# Audio_player_1_0.net
KiCad netlist of a schematic drawn in EAGLE
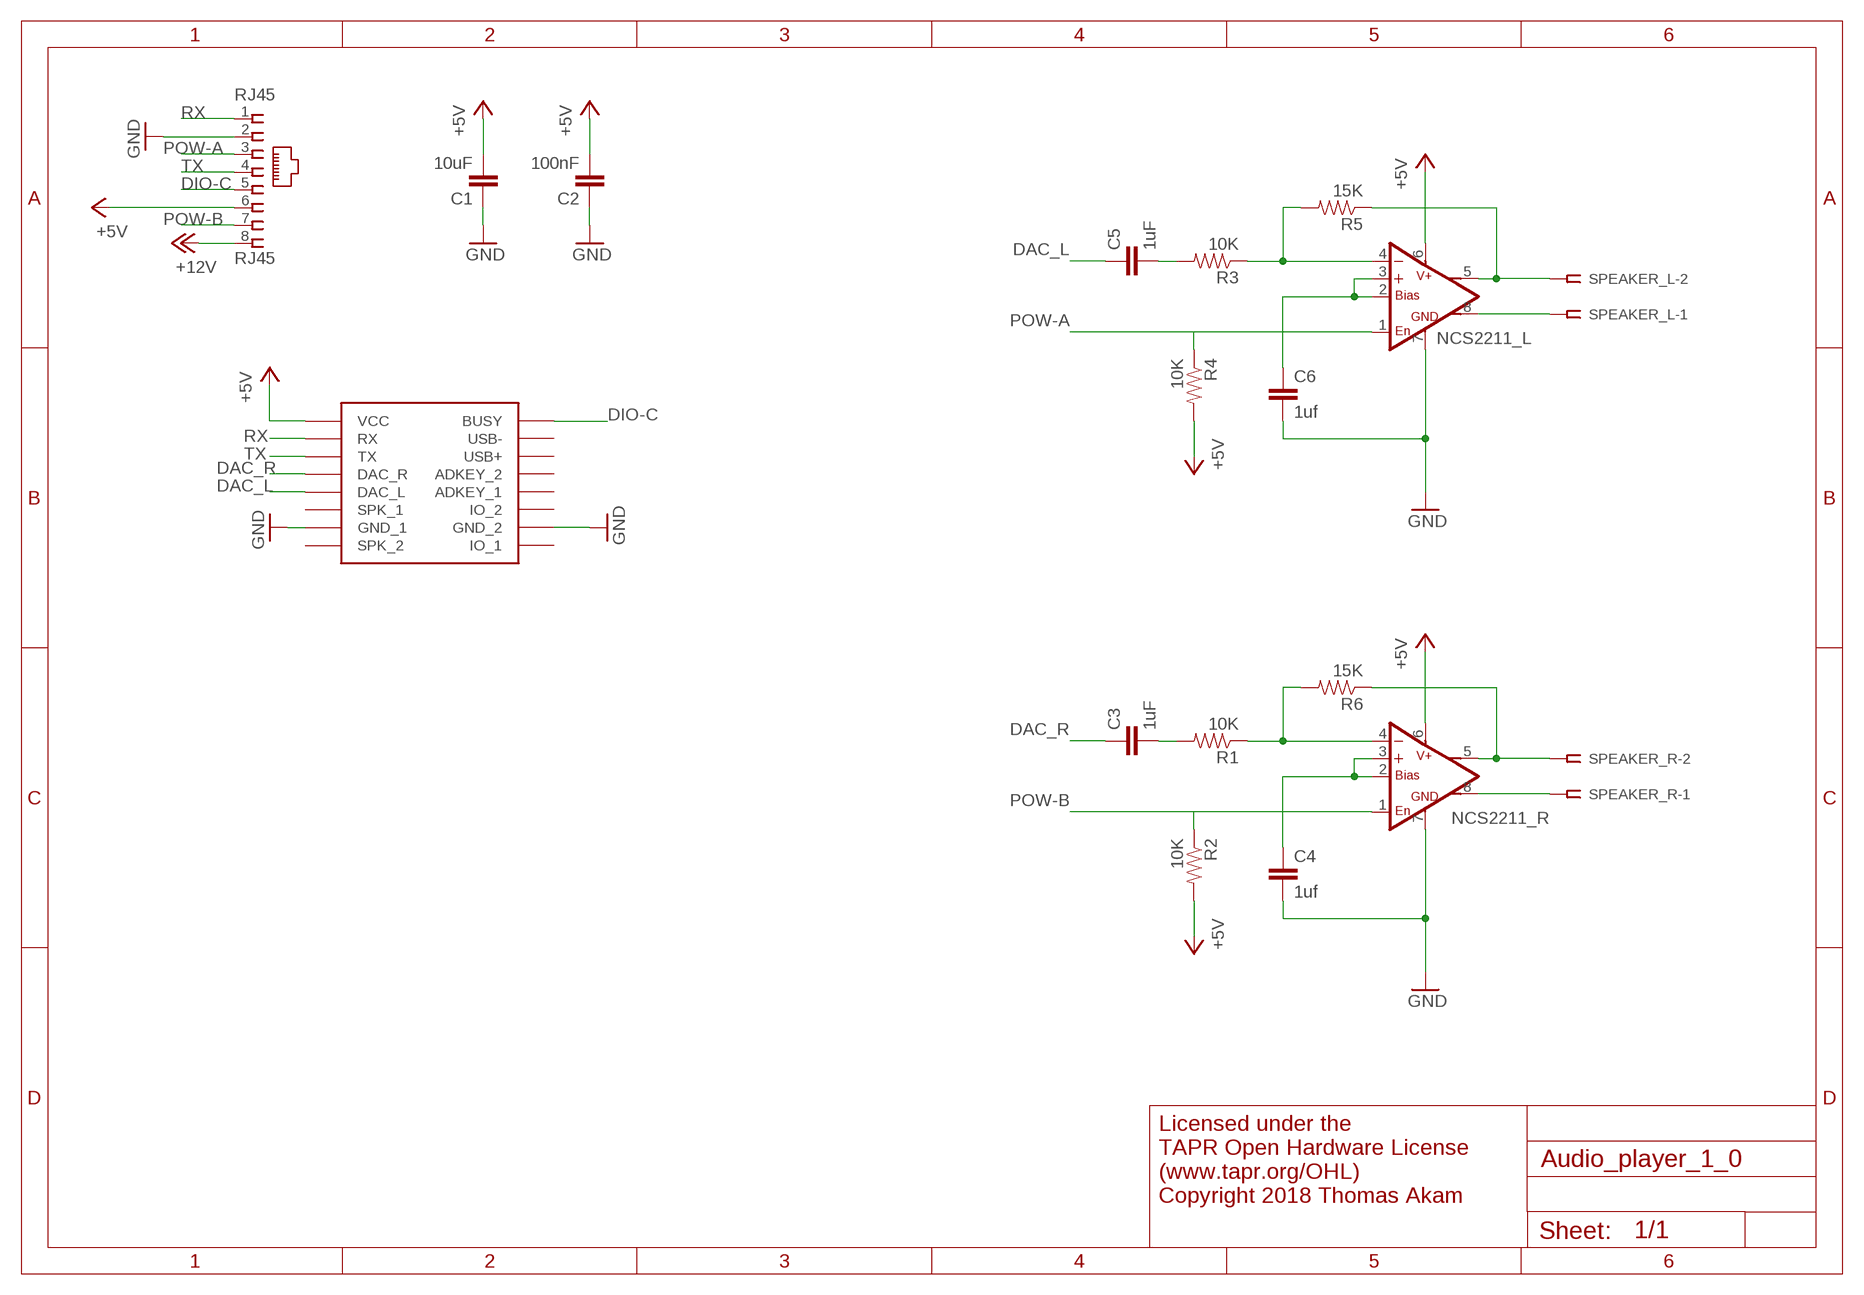
[diagram p0: schematic, sheet 1]

(export (version "E")
  (design (tool "Eeschema 10.0.6"))
  (components
    (comp (ref "C1")
      (value "10uF")
      (footprint "eagle-import:C0805")
      (libsource (lib "eagle-import") (part "C-EUC0805"))
    )
    (comp (ref "C2")
      (value "100nF")
      (footprint "eagle-import:C0805")
      (libsource (lib "eagle-import") (part "C-EUC0805"))
    )
    (comp (ref "C3")
      (value "1uF")
      (footprint "eagle-import:C0805")
      (libsource (lib "eagle-import") (part "C-EUC0805"))
    )
    (comp (ref "C4")
      (value "1uf")
      (footprint "eagle-import:C0805")
      (libsource (lib "eagle-import") (part "C-EUC0805"))
    )
    (comp (ref "C5")
      (value "1uF")
      (footprint "eagle-import:C0805")
      (libsource (lib "eagle-import") (part "C-EUC0805"))
    )
    (comp (ref "C6")
      (value "1uf")
      (footprint "eagle-import:C0805")
      (libsource (lib "eagle-import") (part "C-EUC0805"))
    )
    (comp (ref "NCS2211_L")
      (value "NCS22111M")
      (footprint "eagle-import:SO08")
      (libsource (lib "eagle-import") (part "NCS2211M1"))
    )
    (comp (ref "NCS2211_R")
      (value "NCS22111M")
      (footprint "eagle-import:SO08")
      (libsource (lib "eagle-import") (part "NCS2211M1"))
    )
    (comp (ref "R1")
      (value "10K")
      (footprint "eagle-import:0805")
      (libsource (lib "eagle-import") (part "0.3OHM-1/8W-1%(0805)"))
    )
    (comp (ref "R2")
      (value "10K")
      (footprint "eagle-import:0805")
      (libsource (lib "eagle-import") (part "0.3OHM-1/8W-1%(0805)"))
    )
    (comp (ref "R3")
      (value "10K")
      (footprint "eagle-import:0805")
      (libsource (lib "eagle-import") (part "0.3OHM-1/8W-1%(0805)"))
    )
    (comp (ref "R4")
      (value "10K")
      (footprint "eagle-import:0805")
      (libsource (lib "eagle-import") (part "0.3OHM-1/8W-1%(0805)"))
    )
    (comp (ref "R5")
      (value "15K")
      (footprint "eagle-import:0805")
      (libsource (lib "eagle-import") (part "0.3OHM-1/8W-1%(0805)"))
    )
    (comp (ref "R6")
      (value "15K")
      (footprint "eagle-import:0805")
      (libsource (lib "eagle-import") (part "0.3OHM-1/8W-1%(0805)"))
    )
    (comp (ref "RJ45")
      (value "RJ45")
      (footprint "eagle-import:RJ45-NO-SHIELD-VERTICAL")
      (libsource (lib "eagle-import") (part "RJ45VERTICAL"))
    )
    (comp (ref "SPEAKER_L")
      (value "SSW-102-02-S-S-RA")
      (footprint "eagle-import:SSW-102-02-S-S-RA")
      (libsource (lib "eagle-import") (part "SSW-102-02-S-S-RA"))
    )
    (comp (ref "SPEAKER_R")
      (value "SSW-102-02-S-S-RA")
      (footprint "eagle-import:SSW-102-02-S-S-RA")
      (libsource (lib "eagle-import") (part "SSW-102-02-S-S-RA"))
    )
    (comp (ref "U$1")
      (value "DFPLAYER")
      (footprint "eagle-import:DFPLAYER")
      (libsource (lib "eagle-import") (part "DFPLAYER"))
    )
  )
  (nets
    (net (code "1") (name "+5V") (class "Default")
      (node (ref "C1") (pin "2") (pinfunction "2_2") (pintype "passive"))
      (node (ref "C2") (pin "2") (pinfunction "2_2") (pintype "passive"))
      (node (ref "NCS2211_L") (pin "6") (pinfunction "VS_6") (pintype "power_in"))
      (node (ref "NCS2211_R") (pin "6") (pinfunction "VS_6") (pintype "power_in"))
      (node (ref "R2") (pin "2") (pinfunction "2_2") (pintype "passive"))
      (node (ref "R4") (pin "2") (pinfunction "2_2") (pintype "passive"))
      (node (ref "RJ45") (pin "6") (pinfunction "6_6") (pintype "passive"))
      (node (ref "U$1") (pin "VCC") (pinfunction "VCC_VCC") (pintype "bidirectional"))
    )
    (net (code "2") (name "+12V") (class "Default")
      (node (ref "RJ45") (pin "8") (pinfunction "8_8") (pintype "passive"))
    )
    (net (code "3") (name "/DAC_L") (class "Default")
      (node (ref "C5") (pin "1") (pinfunction "1_1") (pintype "passive"))
      (node (ref "U$1") (pin "DAC_L") (pinfunction "DAC_L_DAC_L") (pintype "bidirectional"))
    )
    (net (code "4") (name "/DAC_R") (class "Default")
      (node (ref "C3") (pin "1") (pinfunction "1_1") (pintype "passive"))
      (node (ref "U$1") (pin "DAC_R") (pinfunction "DAC_R_DAC_R") (pintype "bidirectional"))
    )
    (net (code "5") (name "/DIO-C") (class "Default")
      (node (ref "RJ45") (pin "5") (pinfunction "5_5") (pintype "passive"))
      (node (ref "U$1") (pin "BUSY") (pinfunction "BUSY_BUSY") (pintype "bidirectional"))
    )
    (net (code "6") (name "/POW-A") (class "Default")
      (node (ref "NCS2211_L") (pin "1") (pinfunction "ENABLE_1") (pintype "passive"))
      (node (ref "R4") (pin "1") (pinfunction "1_1") (pintype "passive"))
      (node (ref "RJ45") (pin "3") (pinfunction "3_3") (pintype "passive"))
    )
    (net (code "7") (name "/POW-B") (class "Default")
      (node (ref "NCS2211_R") (pin "1") (pinfunction "ENABLE_1") (pintype "passive"))
      (node (ref "R2") (pin "1") (pinfunction "1_1") (pintype "passive"))
      (node (ref "RJ45") (pin "7") (pinfunction "7_7") (pintype "passive"))
    )
    (net (code "8") (name "/RX") (class "Default")
      (node (ref "RJ45") (pin "1") (pinfunction "1_1") (pintype "passive"))
      (node (ref "U$1") (pin "RX") (pinfunction "RX_RX") (pintype "bidirectional"))
    )
    (net (code "9") (name "/TX") (class "Default")
      (node (ref "RJ45") (pin "4") (pinfunction "4_4") (pintype "passive"))
      (node (ref "U$1") (pin "TX") (pinfunction "TX_TX") (pintype "bidirectional"))
    )
    (net (code "10") (name "GND") (class "Default")
      (node (ref "C1") (pin "1") (pinfunction "1_1") (pintype "passive"))
      (node (ref "C2") (pin "1") (pinfunction "1_1") (pintype "passive"))
      (node (ref "C4") (pin "2") (pinfunction "2_2") (pintype "passive"))
      (node (ref "C6") (pin "2") (pinfunction "2_2") (pintype "passive"))
      (node (ref "NCS2211_L") (pin "7") (pinfunction "GND_7") (pintype "power_in"))
      (node (ref "NCS2211_R") (pin "7") (pinfunction "GND_7") (pintype "power_in"))
      (node (ref "RJ45") (pin "2") (pinfunction "2_2") (pintype "passive"))
      (node (ref "U$1") (pin "GND_1") (pinfunction "GND_1_GND_1") (pintype "bidirectional"))
      (node (ref "U$1") (pin "GND_2") (pinfunction "GND_2_GND_2") (pintype "bidirectional"))
    )
    (net (code "11") (name "Net-(C3-Pad2)") (class "Default")
      (node (ref "C3") (pin "2") (pinfunction "2_2") (pintype "passive"))
      (node (ref "R1") (pin "2") (pinfunction "2_2") (pintype "passive"))
    )
    (net (code "12") (name "Net-(C5-Pad2)") (class "Default")
      (node (ref "C5") (pin "2") (pinfunction "2_2") (pintype "passive"))
      (node (ref "R3") (pin "2") (pinfunction "2_2") (pintype "passive"))
    )
    (net (code "13") (name "Net-(NCS2211_L-+IN)") (class "Default")
      (node (ref "C6") (pin "1") (pinfunction "1_1") (pintype "passive"))
      (node (ref "NCS2211_L") (pin "2") (pinfunction "BIAS_2") (pintype "passive"))
      (node (ref "NCS2211_L") (pin "3") (pinfunction "+IN_3") (pintype "input"))
    )
    (net (code "14") (name "Net-(NCS2211_L-+OUT)") (class "Default")
      (node (ref "NCS2211_L") (pin "5") (pinfunction "+OUT_5") (pintype "passive"))
      (node (ref "R5") (pin "1") (pinfunction "1_1") (pintype "passive"))
      (node (ref "SPEAKER_L") (pin "2") (pinfunction "1_2") (pintype "passive"))
    )
    (net (code "15") (name "Net-(NCS2211_L--IN)") (class "Default")
      (node (ref "NCS2211_L") (pin "4") (pinfunction "-IN_4") (pintype "input"))
      (node (ref "R3") (pin "1") (pinfunction "1_1") (pintype "passive"))
      (node (ref "R5") (pin "2") (pinfunction "2_2") (pintype "passive"))
    )
    (net (code "16") (name "Net-(NCS2211_L--OUT)") (class "Default")
      (node (ref "NCS2211_L") (pin "8") (pinfunction "-OUT_8") (pintype "output"))
      (node (ref "SPEAKER_L") (pin "1") (pinfunction "1_1") (pintype "passive"))
    )
    (net (code "17") (name "Net-(NCS2211_R-+IN)") (class "Default")
      (node (ref "C4") (pin "1") (pinfunction "1_1") (pintype "passive"))
      (node (ref "NCS2211_R") (pin "2") (pinfunction "BIAS_2") (pintype "passive"))
      (node (ref "NCS2211_R") (pin "3") (pinfunction "+IN_3") (pintype "input"))
    )
    (net (code "18") (name "Net-(NCS2211_R-+OUT)") (class "Default")
      (node (ref "NCS2211_R") (pin "5") (pinfunction "+OUT_5") (pintype "passive"))
      (node (ref "R6") (pin "1") (pinfunction "1_1") (pintype "passive"))
      (node (ref "SPEAKER_R") (pin "2") (pinfunction "1_2") (pintype "passive"))
    )
    (net (code "19") (name "Net-(NCS2211_R--IN)") (class "Default")
      (node (ref "NCS2211_R") (pin "4") (pinfunction "-IN_4") (pintype "input"))
      (node (ref "R1") (pin "1") (pinfunction "1_1") (pintype "passive"))
      (node (ref "R6") (pin "2") (pinfunction "2_2") (pintype "passive"))
    )
    (net (code "20") (name "Net-(NCS2211_R--OUT)") (class "Default")
      (node (ref "NCS2211_R") (pin "8") (pinfunction "-OUT_8") (pintype "output"))
      (node (ref "SPEAKER_R") (pin "1") (pinfunction "1_1") (pintype "passive"))
    )
    (net (code "21") (name "unconnected-(U$1-ADKEY_1-PadADKEY1)") (class "Default")
      (node (ref "U$1") (pin "ADKEY1") (pinfunction "ADKEY_1_ADKEY1") (pintype "bidirectional"))
    )
    (net (code "22") (name "unconnected-(U$1-ADKEY_2-PadADKEY2)") (class "Default")
      (node (ref "U$1") (pin "ADKEY2") (pinfunction "ADKEY_2_ADKEY2") (pintype "bidirectional"))
    )
    (net (code "23") (name "unconnected-(U$1-IO_1-PadIO1)") (class "Default")
      (node (ref "U$1") (pin "IO1") (pinfunction "IO_1_IO1") (pintype "bidirectional"))
    )
    (net (code "24") (name "unconnected-(U$1-IO_2-PadIO2)") (class "Default")
      (node (ref "U$1") (pin "IO2") (pinfunction "IO_2_IO2") (pintype "bidirectional"))
    )
    (net (code "25") (name "unconnected-(U$1-PadUSB+)") (class "Default")
      (node (ref "U$1") (pin "USB+") (pinfunction "USB+_USB+") (pintype "bidirectional"))
    )
    (net (code "26") (name "unconnected-(U$1-PadUSB-)") (class "Default")
      (node (ref "U$1") (pin "USB-") (pinfunction "USB-_USB-") (pintype "bidirectional"))
    )
    (net (code "27") (name "unconnected-(U$1-SPK_1-PadSPK1)") (class "Default")
      (node (ref "U$1") (pin "SPK1") (pinfunction "SPK_1_SPK1") (pintype "bidirectional"))
    )
    (net (code "28") (name "unconnected-(U$1-SPK_2-PadSPK2)") (class "Default")
      (node (ref "U$1") (pin "SPK2") (pinfunction "SPK_2_SPK2") (pintype "bidirectional"))
    )
  )
)
